# Power_Supplies_and_regulator.net
KiCad netlist of a schematic drawn in Altium Designer
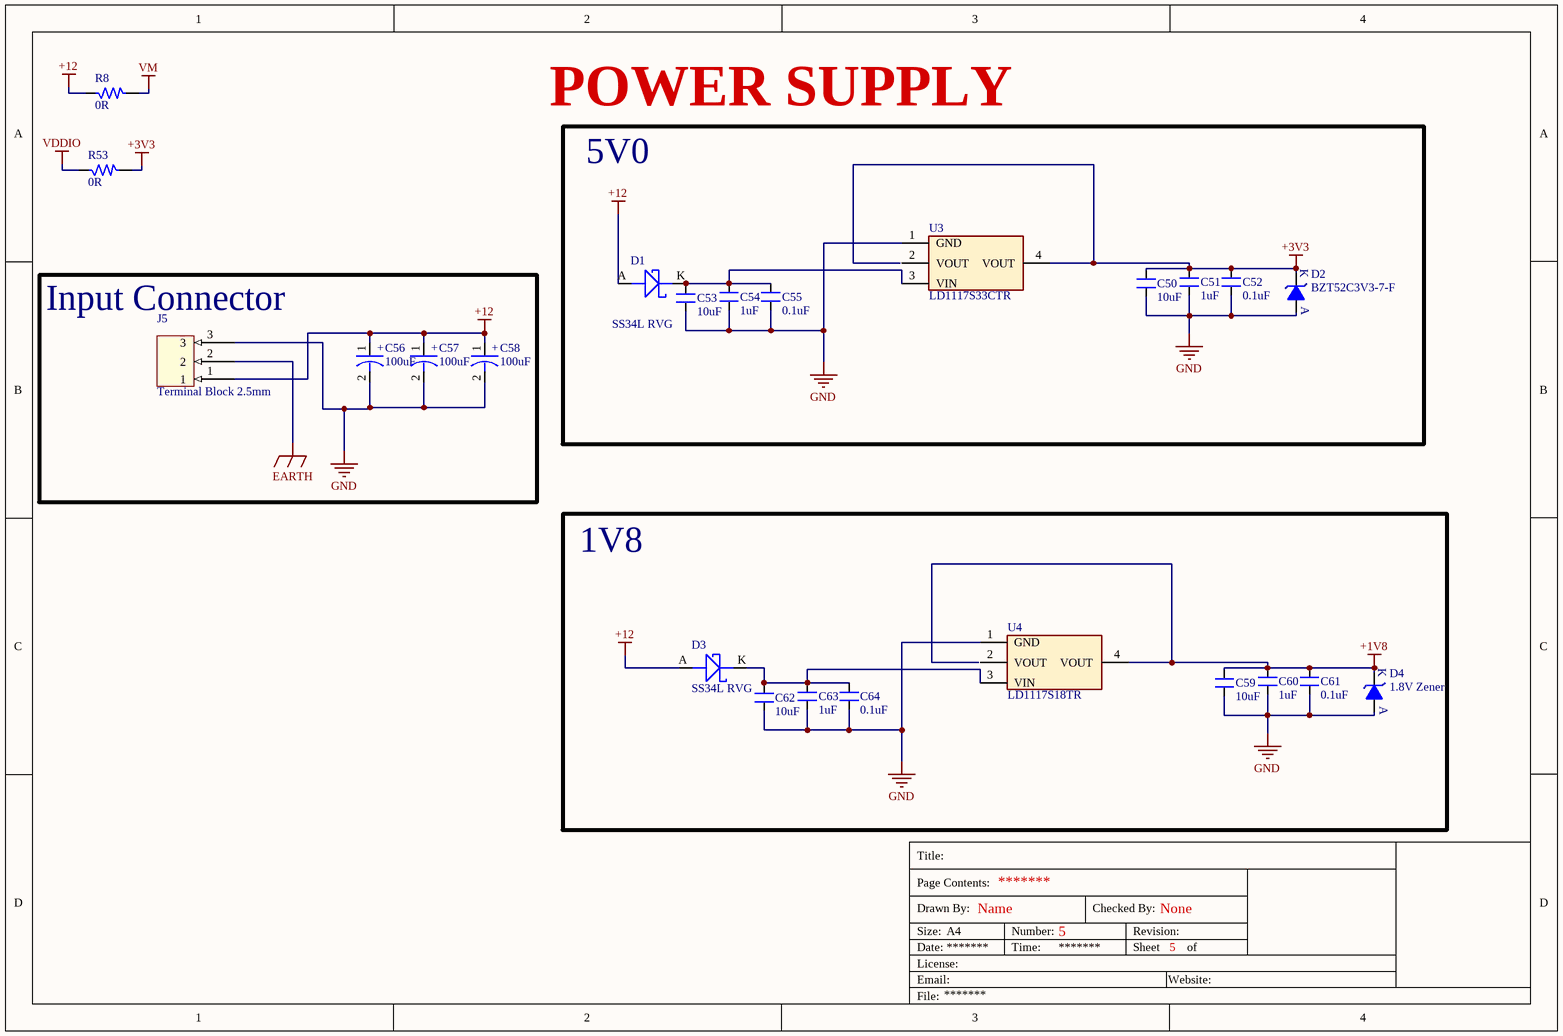
[diagram p0: Power Supplies and regulator.SchDoc]

(export (version "E")
  (design (tool "Eeschema 10.0.6"))
  (components
    (comp (ref "C50")
      (value "10uF")
      (footprint "CAP_1206")
      (description "10µF ±10% 50V Ceramic Capacitor X7R 1206 (3216 Metric)")
      (fields
        (field (name "MANUFACTURER") "KEMET")
        (field (name "MANUFACTURER PART NUMBER") "CL31B106KBHNNNE")
      )
      (libsource (lib "ESTEEMPCBLIB") (part "CAP_10uF-50V-10%-1206"))
    )
    (comp (ref "C51")
      (value "1uF")
      (footprint "CAP_0805")
      (description "1µF ±5% 50V Ceramic Capacitor X7R 0805 (2012 Metric)")
      (fields
        (field (name "MANUFACTURER") "Samsung")
        (field (name "MANUFACTURER PART NUMBER") "CC0805JKX7R9BB105")
      )
      (libsource (lib "ESTEEMPCBLIB") (part "CAP_1uF-50V-5%-0805"))
    )
    (comp (ref "C52")
      (value "0.1uF")
      (footprint "CAP_0805")
      (description "0.1µF ±5% 50V Ceramic Capacitor X7R 0805 (2012 Metric)")
      (fields
        (field (name "MANUFACTURER") "AVX Corporation")
        (field (name "MANUFACTURER PART NUMBER") "08055C104JAT4A")
      )
      (libsource (lib "ESTEEMPCBLIB") (part "CAP_0.1uF-50V-5%-0805"))
    )
    (comp (ref "C53")
      (value "10uF")
      (footprint "CAP_1206")
      (description "10µF ±10% 50V Ceramic Capacitor X7R 1206 (3216 Metric)")
      (fields
        (field (name "MANUFACTURER") "KEMET")
        (field (name "MANUFACTURER PART NUMBER") "CL31B106KBHNNNE")
      )
      (libsource (lib "ESTEEMPCBLIB") (part "CAP_10uF-50V-10%-1206"))
    )
    (comp (ref "C54")
      (value "1uF")
      (footprint "CAP_0805")
      (description "1µF ±5% 50V Ceramic Capacitor X7R 0805 (2012 Metric)")
      (fields
        (field (name "MANUFACTURER") "Samsung")
        (field (name "MANUFACTURER PART NUMBER") "CC0805JKX7R9BB105")
      )
      (libsource (lib "ESTEEMPCBLIB") (part "CAP_1uF-50V-5%-0805"))
    )
    (comp (ref "C55")
      (value "0.1uF")
      (footprint "CAP_0805")
      (description "0.1µF ±5% 50V Ceramic Capacitor X7R 0805 (2012 Metric)")
      (fields
        (field (name "MANUFACTURER") "AVX Corporation")
        (field (name "MANUFACTURER PART NUMBER") "08055C104JAT4A")
      )
      (libsource (lib "ESTEEMPCBLIB") (part "CAP_0.1uF-50V-5%-0805"))
    )
    (comp (ref "C56")
      (value "100uF")
      (footprint "ACAP_P236_D305_H303_RAD")
      (description "100µF 25V Aluminum Electrolytic Capacitors Radial, Can - SMD 1000 Hrs @ 105°C")
      (fields
        (field (name "MANUFACTURER") "Nichicon")
        (field (name "MANUFACTURER PART NUMBER") "UWT1E101MCL1GS")
      )
      (libsource (lib "ESTEEMPCBLIB") (part "CAP-P_100uF-25V-20%-RAD"))
    )
    (comp (ref "C57")
      (value "100uF")
      (footprint "ACAP_P236_D305_H303_RAD")
      (description "100µF 25V Aluminum Electrolytic Capacitors Radial, Can - SMD 1000 Hrs @ 105°C")
      (fields
        (field (name "MANUFACTURER") "Nichicon")
        (field (name "MANUFACTURER PART NUMBER") "UWT1E101MCL1GS")
      )
      (libsource (lib "ESTEEMPCBLIB") (part "CAP-P_100uF-25V-20%-RAD"))
    )
    (comp (ref "C58")
      (value "100uF")
      (footprint "ACAP_P236_D305_H303_RAD")
      (description "100µF 25V Aluminum Electrolytic Capacitors Radial, Can - SMD 1000 Hrs @ 105°C")
      (fields
        (field (name "MANUFACTURER") "Nichicon")
        (field (name "MANUFACTURER PART NUMBER") "UWT1E101MCL1GS")
      )
      (libsource (lib "ESTEEMPCBLIB") (part "CAP-P_100uF-25V-20%-RAD"))
    )
    (comp (ref "C59")
      (value "10uF")
      (footprint "CAP_1206")
      (description "10µF ±10% 50V Ceramic Capacitor X7R 1206 (3216 Metric)")
      (fields
        (field (name "MANUFACTURER") "KEMET")
        (field (name "MANUFACTURER PART NUMBER") "CL31B106KBHNNNE")
      )
      (libsource (lib "ESTEEMPCBLIB") (part "CAP_10uF-50V-10%-1206"))
    )
    (comp (ref "C60")
      (value "1uF")
      (footprint "CAP_0805")
      (description "1µF ±5% 50V Ceramic Capacitor X7R 0805 (2012 Metric)")
      (fields
        (field (name "MANUFACTURER") "Samsung")
        (field (name "MANUFACTURER PART NUMBER") "CC0805JKX7R9BB105")
      )
      (libsource (lib "ESTEEMPCBLIB") (part "CAP_1uF-50V-5%-0805"))
    )
    (comp (ref "C61")
      (value "0.1uF")
      (footprint "CAP_0805")
      (description "0.1µF ±5% 50V Ceramic Capacitor X7R 0805 (2012 Metric)")
      (fields
        (field (name "MANUFACTURER") "AVX Corporation")
        (field (name "MANUFACTURER PART NUMBER") "08055C104JAT4A")
      )
      (libsource (lib "ESTEEMPCBLIB") (part "CAP_0.1uF-50V-5%-0805"))
    )
    (comp (ref "C62")
      (value "10uF")
      (footprint "CAP_1206")
      (description "10µF ±10% 50V Ceramic Capacitor X7R 1206 (3216 Metric)")
      (fields
        (field (name "MANUFACTURER") "KEMET")
        (field (name "MANUFACTURER PART NUMBER") "CL31B106KBHNNNE")
      )
      (libsource (lib "ESTEEMPCBLIB") (part "CAP_10uF-50V-10%-1206"))
    )
    (comp (ref "C63")
      (value "1uF")
      (footprint "CAP_0805")
      (description "1µF ±5% 50V Ceramic Capacitor X7R 0805 (2012 Metric)")
      (fields
        (field (name "MANUFACTURER") "Samsung")
        (field (name "MANUFACTURER PART NUMBER") "CC0805JKX7R9BB105")
      )
      (libsource (lib "ESTEEMPCBLIB") (part "CAP_1uF-50V-5%-0805"))
    )
    (comp (ref "C64")
      (value "0.1uF")
      (footprint "CAP_0805")
      (description "0.1µF ±5% 50V Ceramic Capacitor X7R 0805 (2012 Metric)")
      (fields
        (field (name "MANUFACTURER") "AVX Corporation")
        (field (name "MANUFACTURER PART NUMBER") "08055C104JAT4A")
      )
      (libsource (lib "ESTEEMPCBLIB") (part "CAP_0.1uF-50V-5%-0805"))
    )
    (comp (ref "D1")
      (value "SS34L RVG")
      (footprint "DIO_SMB_DO-214AC")
      (description "Diode Schottky 40V 5A Surface Mount SMA")
      (fields (field (name "MANUFACTURER") "Multicomp"))
      (libsource (lib "ESTEEMPCBLIB") (part "DIO-S_550mV-40V-5A-SMC"))
    )
    (comp (ref "D2")
      (value "BZT52C3V3-7-F")
      (footprint "DIO_SOD-123")
      (description "Zener Diode 3.3V 500mW ±6% Surface Mount SOD-123")
      (fields (field (name "MANUFACTURER") "Diodes Incorporated"))
      (libsource (lib "ESTEEMPCBLIB") (part "DIO-Z_3.3V-500mW-SOD123"))
    )
    (comp (ref "D3")
      (value "SS34L RVG")
      (footprint "DIO_SMB_DO-214AC")
      (description "Diode Schottky 40V 5A Surface Mount SMA")
      (fields (field (name "MANUFACTURER") "Multicomp"))
      (libsource (lib "ESTEEMPCBLIB") (part "DIO-S_550mV-40V-5A-SMC"))
    )
    (comp (ref "D4")
      (value "1.8V Zener")
      (footprint "DIO_DO-213AB_SMD")
      (description "Zener Diode 1.8V 500mW ±5% Surface Mount DO-213AA")
      (libsource (lib "ESTEEMPCBLIB") (part "DIO-Z_1.8V-500mW-DO213AA"))
    )
    (comp (ref "J5")
      (value "Terminal Block 2.5mm")
      (footprint "CON3_100_TB_TH_ST")
      (description "3 Pins, 1 Row 2.54mm Pitch, straight Connector, male")
      (fields
        (field (name "MANUFACTURER PART NUMBER") "1725669")
        (field (name "MANUFACTURER") "Phoenix Contact")
      )
      (libsource (lib "ESTEEMPCBLIB") (part "CON-TB_3X1-100-ST-TH"))
    )
    (comp (ref "R8")
      (value "0R")
      (footprint "RES_1206")
      (description "0 Ohms Jumper 0.25W, 1/4W Chip Resistor 1206 (3216 Metric) Automotive AEC-Q200 Thick Film")
      (fields (field (name "MANUFACTURER") "Walsin") (field (name "MANUFACTURER PART NUMBER") "WR12X000PTL"))
      (libsource (lib "ESTEEMPCBLIB") (part "RES_0R-0.25W-1%-1206"))
    )
    (comp (ref "R53")
      (value "0R")
      (footprint "RES_1206")
      (description "0 Ohms Jumper 0.25W, 1/4W Chip Resistor 1206 (3216 Metric) Automotive AEC-Q200 Thick Film")
      (fields (field (name "MANUFACTURER") "Walsin") (field (name "MANUFACTURER PART NUMBER") "WR12X000PTL"))
      (libsource (lib "ESTEEMPCBLIB") (part "RES_0R-0.25W-1%-1206"))
    )
    (comp (ref "U3")
      (value "LD1117S33CTR")
      (footprint "SOT223_3")
      (description "Linear Voltage Regulator IC 1 Output 800mA SOT-223")
      (fields (field (name "MANUFACTURER") "STMicroelectronics"))
      (libsource (lib "ESTEEMPCBLIB") (part "REG_15V-3.3V-0.9A-12W-SOT223"))
    )
    (comp (ref "U4")
      (value "LD1117S18TR")
      (footprint "SOT223_3")
      (description "LDO Voltage Regulators 1.8V 0.8A Positive")
      (fields (field (name "MANUFACTURER") "STMicroelectronics"))
      (libsource (lib "ESTEEMPCBLIB") (part "REG_15V-1.8V-0.8A-1.4W-SOT223"))
    )
  )
  (nets
    (net (code "1") (name "+1V8") (class "Default")
      (node (ref "C59") (pin "2") (pinfunction "2_2") (pintype "passive"))
      (node (ref "C60") (pin "2") (pinfunction "2_2") (pintype "passive"))
      (node (ref "C61") (pin "2") (pinfunction "2_2") (pintype "passive"))
      (node (ref "D4") (pin "K") (pinfunction "K_K") (pintype "passive"))
      (node (ref "U4") (pin "4") (pinfunction "VOUT_4") (pintype "passive"))
    )
    (net (code "2") (name "+3V3") (class "Default")
      (node (ref "C50") (pin "2") (pinfunction "2_2") (pintype "passive"))
      (node (ref "C51") (pin "2") (pinfunction "2_2") (pintype "passive"))
      (node (ref "C52") (pin "2") (pinfunction "2_2") (pintype "passive"))
      (node (ref "D2") (pin "K") (pinfunction "K_K") (pintype "passive"))
      (node (ref "R53") (pin "2") (pinfunction "2_2") (pintype "passive"))
      (node (ref "U3") (pin "4") (pinfunction "VOUT_4") (pintype "passive"))
    )
    (net (code "3") (name "+12") (class "Default")
      (node (ref "C56") (pin "1") (pinfunction "1_1") (pintype "passive"))
      (node (ref "C57") (pin "1") (pinfunction "1_1") (pintype "passive"))
      (node (ref "C58") (pin "1") (pinfunction "1_1") (pintype "passive"))
      (node (ref "D1") (pin "A") (pinfunction "A_A") (pintype "passive"))
      (node (ref "D3") (pin "A") (pinfunction "A_A") (pintype "passive"))
      (node (ref "J5") (pin "1") (pinfunction "1_1") (pintype "input"))
      (node (ref "R8") (pin "1") (pinfunction "1_1") (pintype "passive"))
    )
    (net (code "4") (name "EARTH") (class "Default")
      (node (ref "J5") (pin "2") (pinfunction "2_2") (pintype "input"))
    )
    (net (code "5") (name "GND") (class "Default")
      (node (ref "C50") (pin "1") (pinfunction "1_1") (pintype "passive"))
      (node (ref "C51") (pin "1") (pinfunction "1_1") (pintype "passive"))
      (node (ref "C52") (pin "1") (pinfunction "1_1") (pintype "passive"))
      (node (ref "C53") (pin "1") (pinfunction "1_1") (pintype "passive"))
      (node (ref "C54") (pin "1") (pinfunction "1_1") (pintype "passive"))
      (node (ref "C55") (pin "1") (pinfunction "1_1") (pintype "passive"))
      (node (ref "C56") (pin "2") (pinfunction "2_2") (pintype "passive"))
      (node (ref "C57") (pin "2") (pinfunction "2_2") (pintype "passive"))
      (node (ref "C58") (pin "2") (pinfunction "2_2") (pintype "passive"))
      (node (ref "C59") (pin "1") (pinfunction "1_1") (pintype "passive"))
      (node (ref "C60") (pin "1") (pinfunction "1_1") (pintype "passive"))
      (node (ref "C61") (pin "1") (pinfunction "1_1") (pintype "passive"))
      (node (ref "C62") (pin "1") (pinfunction "1_1") (pintype "passive"))
      (node (ref "C63") (pin "1") (pinfunction "1_1") (pintype "passive"))
      (node (ref "C64") (pin "1") (pinfunction "1_1") (pintype "passive"))
      (node (ref "D2") (pin "A") (pinfunction "A_A") (pintype "passive"))
      (node (ref "D4") (pin "A") (pinfunction "A_A") (pintype "passive"))
      (node (ref "J5") (pin "3") (pinfunction "3_3") (pintype "input"))
      (node (ref "U3") (pin "1") (pinfunction "GND_1") (pintype "passive"))
      (node (ref "U4") (pin "1") (pinfunction "GND_1") (pintype "passive"))
    )
    (net (code "6") (name "Net-(U3-VIN)") (class "Default")
      (node (ref "C53") (pin "2") (pinfunction "2_2") (pintype "passive"))
      (node (ref "C54") (pin "2") (pinfunction "2_2") (pintype "passive"))
      (node (ref "C55") (pin "2") (pinfunction "2_2") (pintype "passive"))
      (node (ref "D1") (pin "K") (pinfunction "K_K") (pintype "passive"))
      (node (ref "U3") (pin "3") (pinfunction "VIN_3") (pintype "passive"))
    )
    (net (code "7") (name "Net-(U4-VIN)") (class "Default")
      (node (ref "C62") (pin "2") (pinfunction "2_2") (pintype "passive"))
      (node (ref "C63") (pin "2") (pinfunction "2_2") (pintype "passive"))
      (node (ref "C64") (pin "2") (pinfunction "2_2") (pintype "passive"))
      (node (ref "D3") (pin "K") (pinfunction "K_K") (pintype "passive"))
      (node (ref "U4") (pin "3") (pinfunction "VIN_3") (pintype "passive"))
    )
    (net (code "8") (name "VDDIO") (class "Default")
      (node (ref "R53") (pin "1") (pinfunction "1_1") (pintype "passive"))
    )
    (net (code "9") (name "VM") (class "Default")
      (node (ref "R8") (pin "2") (pinfunction "2_2") (pintype "passive"))
    )
    (net (code "10") (name "unconnected-(U3-VOUT-Pad2)") (class "Default")
      (node (ref "U3") (pin "2") (pinfunction "VOUT_2") (pintype "passive"))
    )
    (net (code "11") (name "unconnected-(U4-VOUT-Pad2)") (class "Default")
      (node (ref "U4") (pin "2") (pinfunction "VOUT_2") (pintype "passive"))
    )
  )
)
